# axiom_beta_power_adapter_v0_2_f7c9b04d.net
KiCad netlist of a schematic drawn in EAGLE
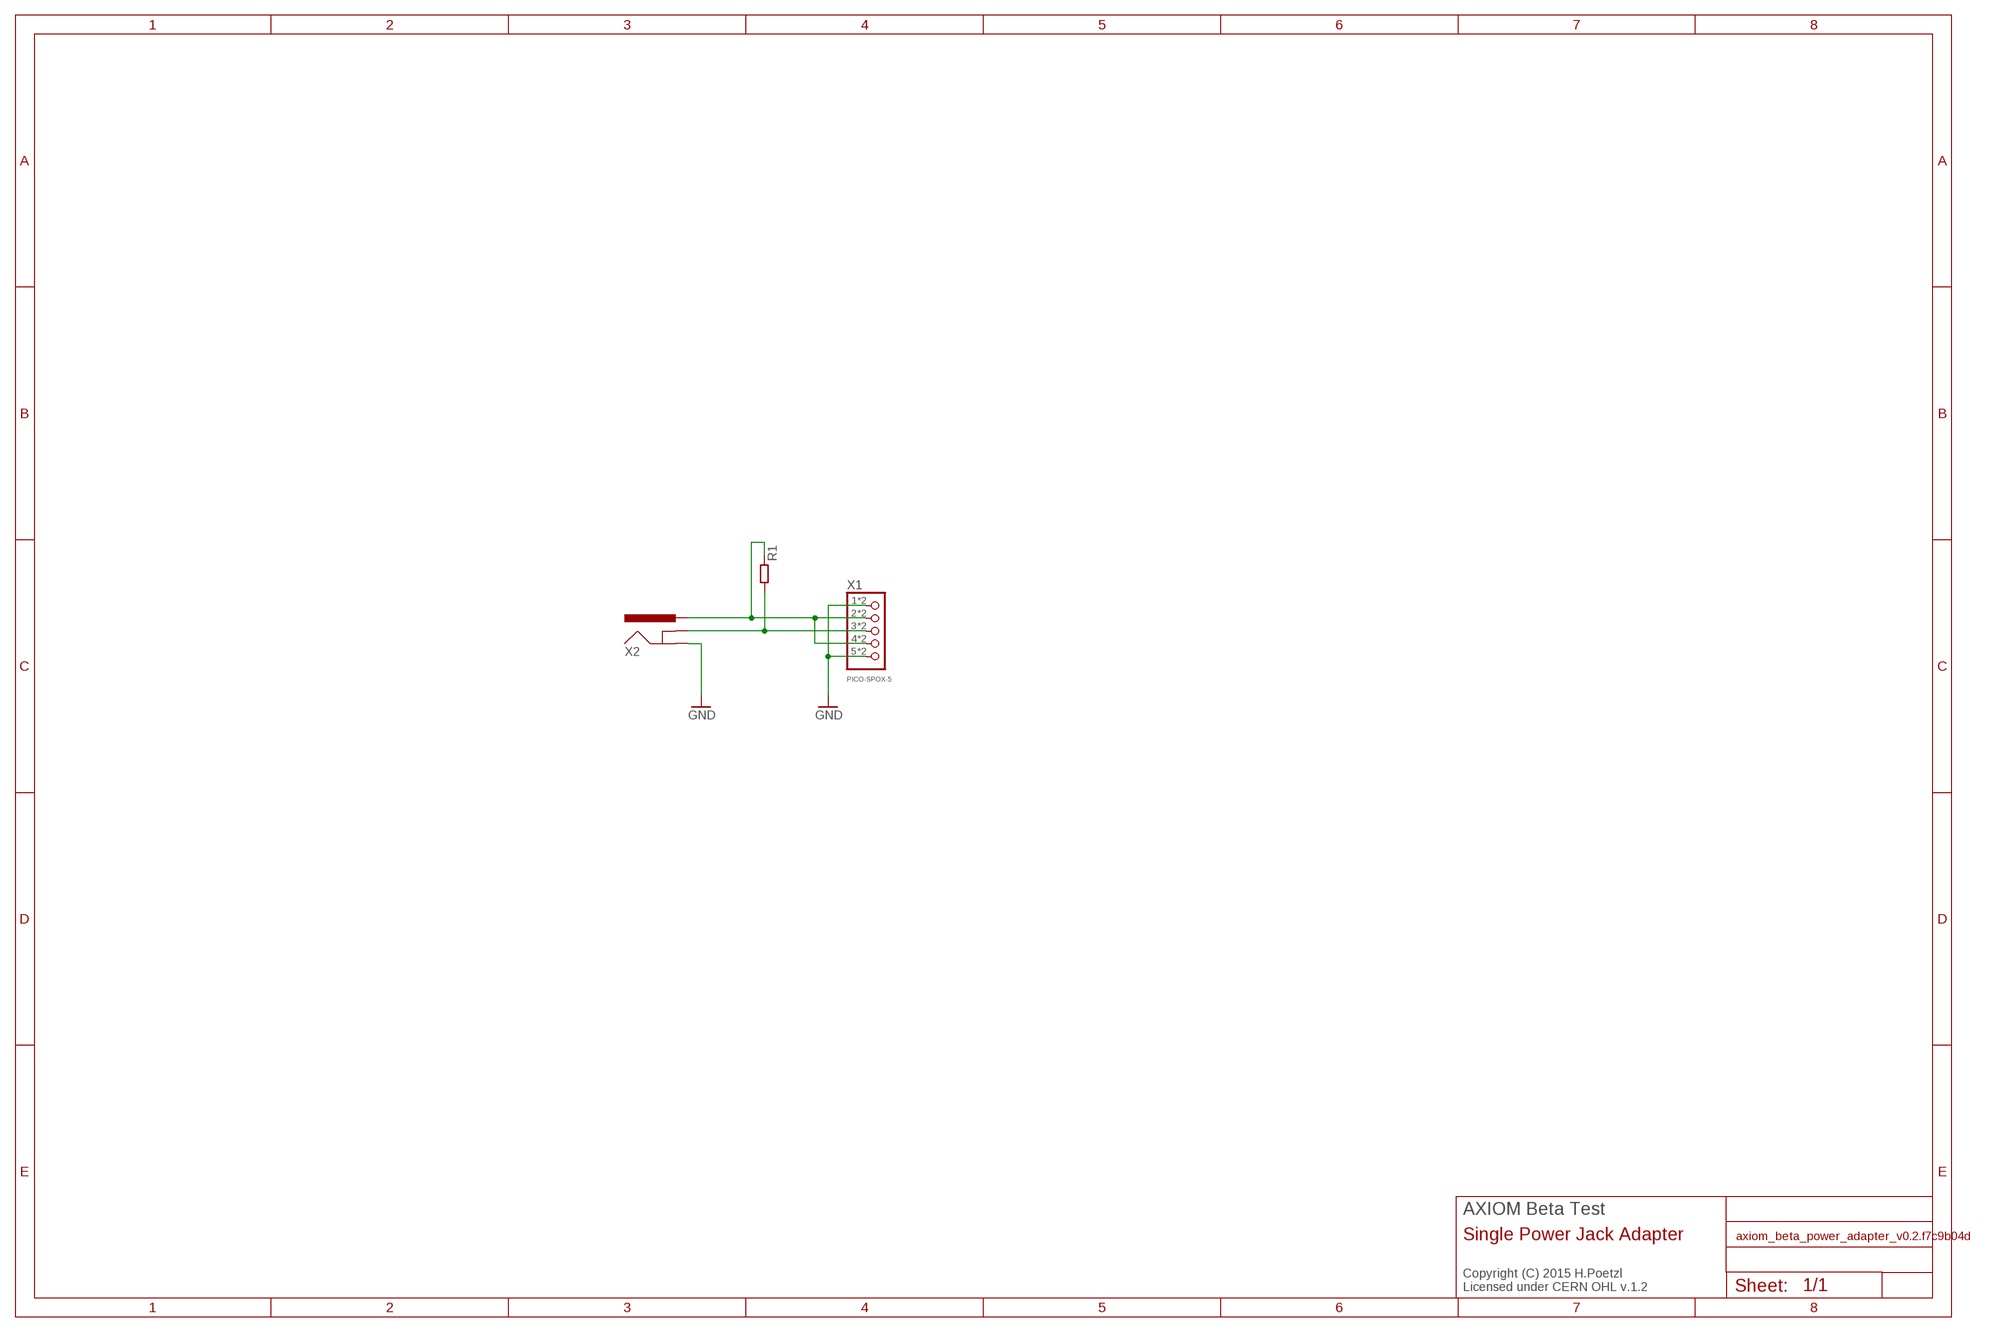
[diagram p0: schematic, sheet 1]

(export (version "E")
  (design (tool "Eeschema 10.0.6"))
  (components
    (comp (ref "R1")
      (value "R0402-B")
      (footprint "eagle-import:0402-B")
      (libsource (lib "eagle-import") (part "R0402-B"))
    )
    (comp (ref "X1")
      (value "PICO-SPOX-5")
      (footprint "eagle-import:PICO-SPOX-5")
      (libsource (lib "eagle-import") (part "PICO-SPOX-5"))
    )
    (comp (ref "X2")
      (value "POWER_JACKPTH_N")
      (footprint "eagle-import:POWER_JACK_PTH_NARROW")
      (libsource (lib "eagle-import") (part "POWER_JACKPTH_N"))
    )
  )
  (nets
    (net (code "1") (name "GND") (class "Default")
      (node (ref "X1") (pin "1") (pinfunction "1_1") (pintype "passive"))
      (node (ref "X1") (pin "1A") (pinfunction "1_1A") (pintype "passive"))
      (node (ref "X1") (pin "5") (pinfunction "5_5") (pintype "passive"))
      (node (ref "X1") (pin "5A") (pinfunction "5_5A") (pintype "passive"))
      (node (ref "X2") (pin "GND") (pinfunction "GND_GND") (pintype "bidirectional"))
    )
    (net (code "2") (name "Net-(R1-Pad1)") (class "Default")
      (node (ref "R1") (pin "1") (pinfunction "1_1") (pintype "passive"))
      (node (ref "X1") (pin "2") (pinfunction "2_2") (pintype "passive"))
      (node (ref "X1") (pin "2A") (pinfunction "2_2A") (pintype "passive"))
      (node (ref "X1") (pin "4") (pinfunction "4_4") (pintype "passive"))
      (node (ref "X1") (pin "4A") (pinfunction "4_4A") (pintype "passive"))
      (node (ref "X2") (pin "PWR") (pinfunction "PWR_PWR") (pintype "bidirectional"))
    )
    (net (code "3") (name "Net-(X2-GNDBREAK)") (class "Default")
      (node (ref "R1") (pin "2") (pinfunction "2_2") (pintype "passive"))
      (node (ref "X1") (pin "3") (pinfunction "3_3") (pintype "passive"))
      (node (ref "X1") (pin "3A") (pinfunction "3_3A") (pintype "passive"))
      (node (ref "X2") (pin "SHUNT") (pinfunction "GNDBREAK_SHUNT") (pintype "bidirectional"))
    )
  )
)
